# Power_Input.net
KiCad netlist of a schematic drawn in Altium Designer
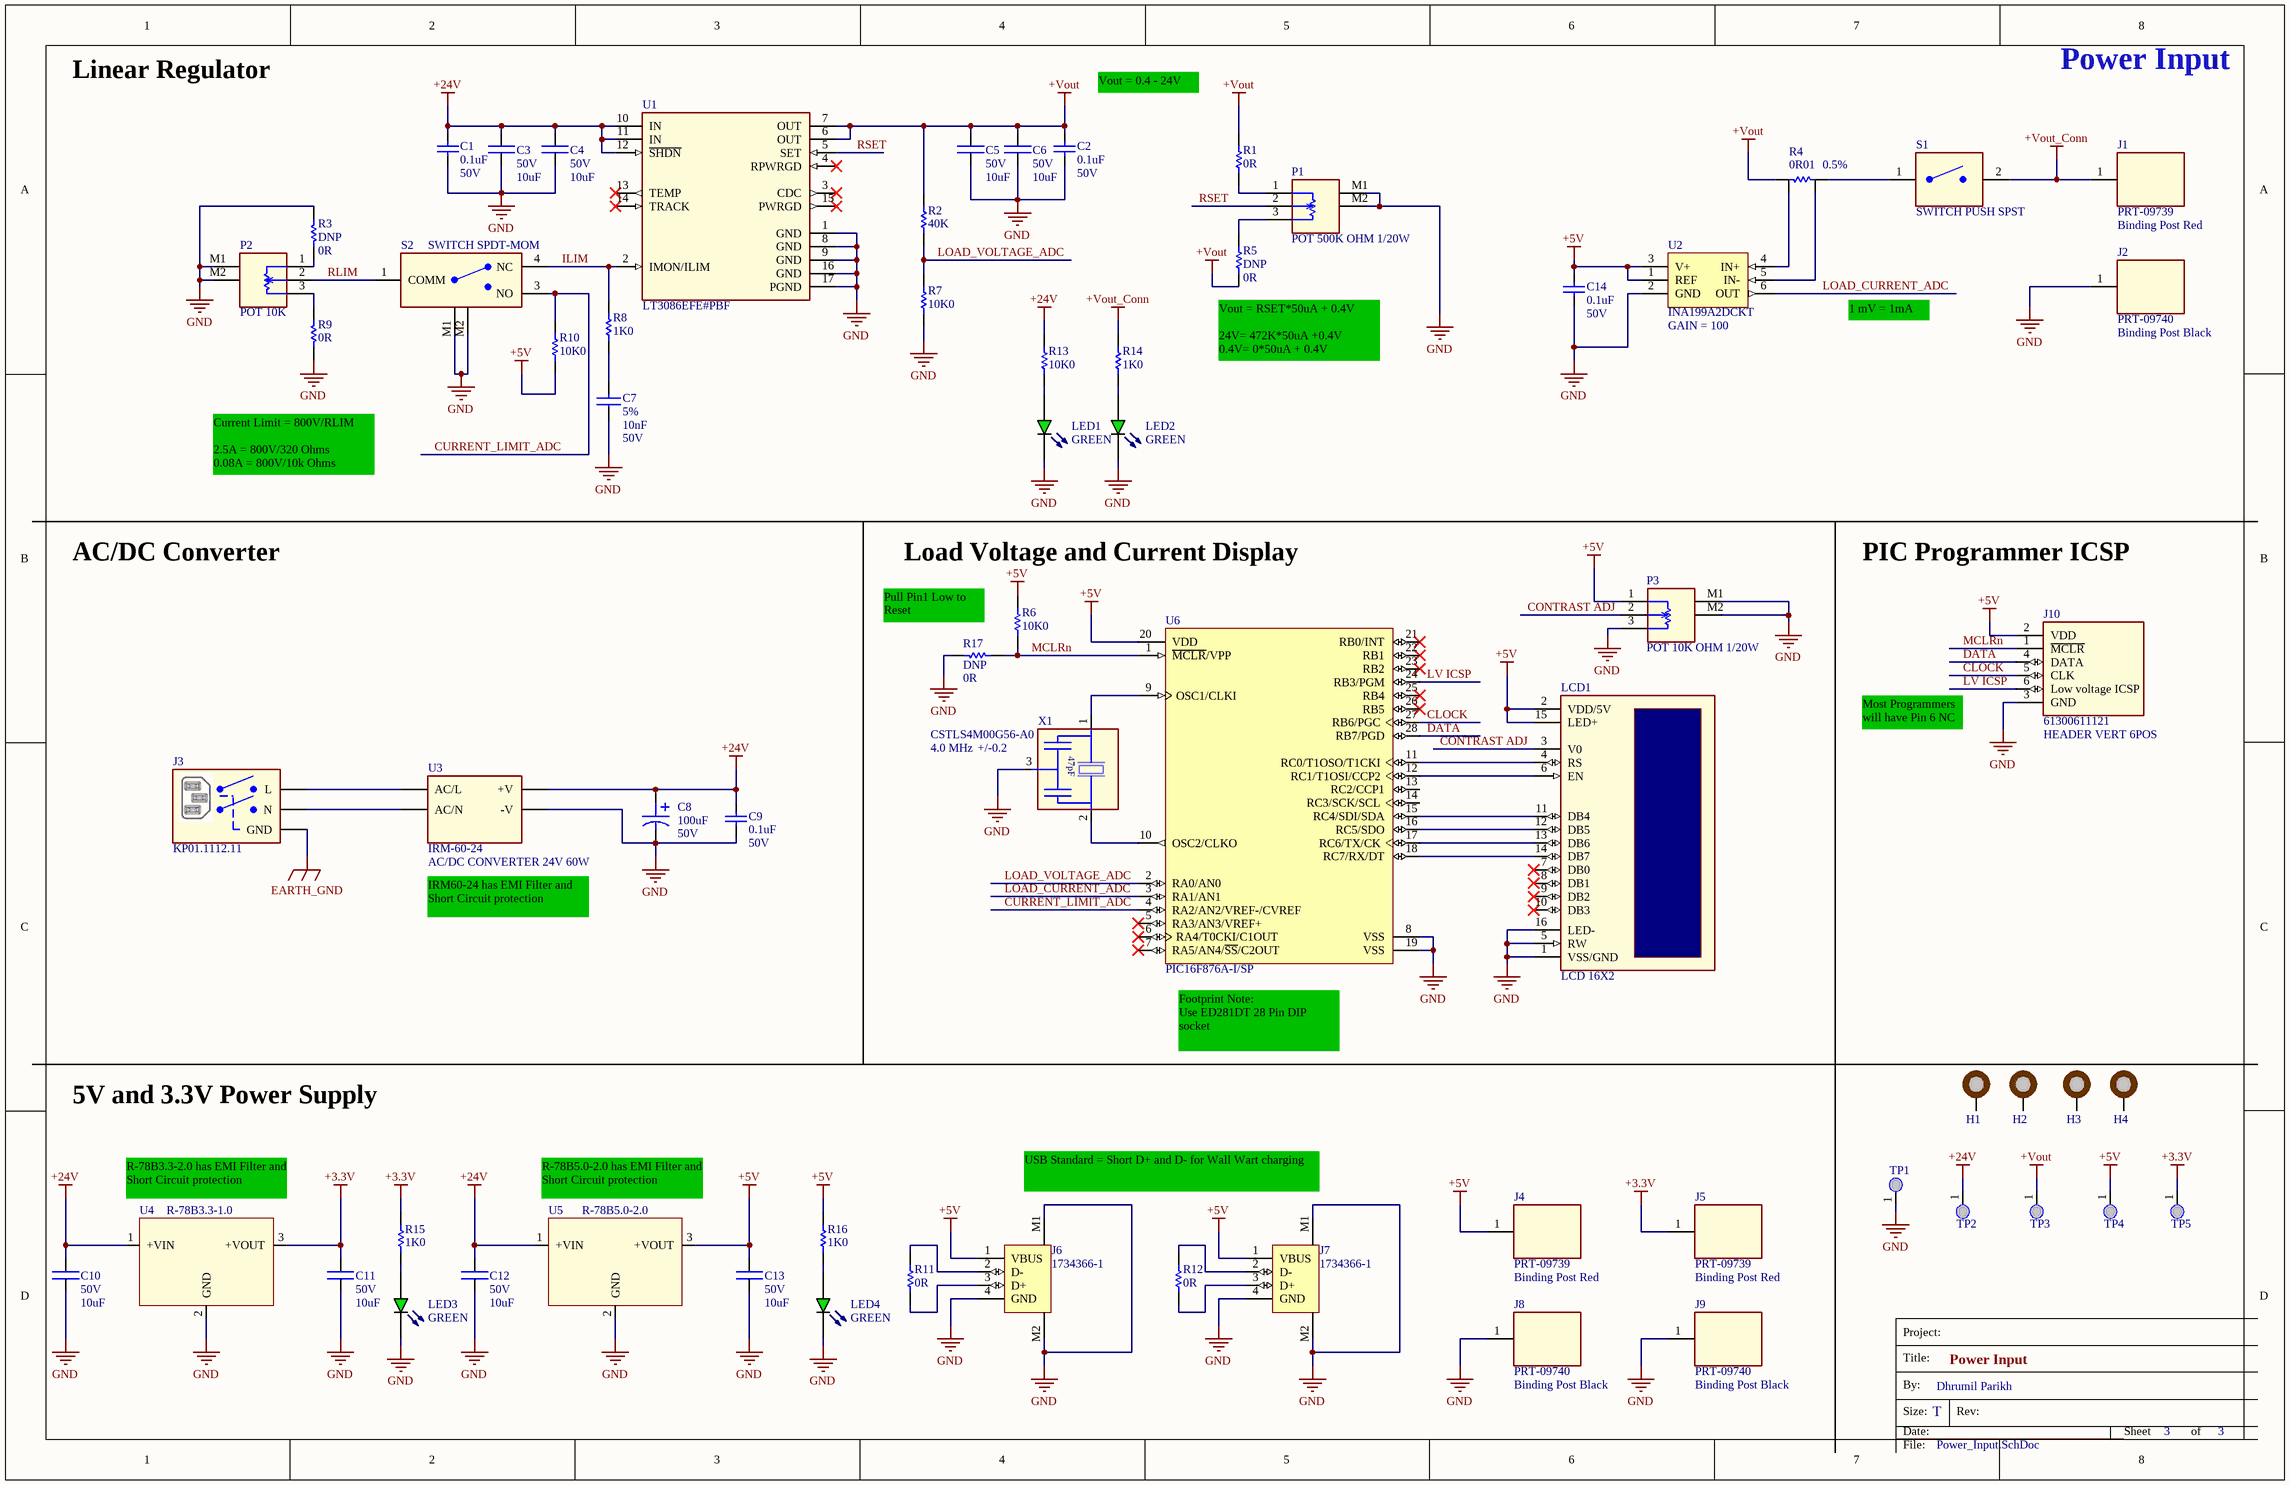
[diagram p0: Power_Input.SchDoc]

(export (version "E")
  (design (tool "Eeschema 10.0.6"))
  (components
    (comp (ref "C1")
      (value "0.1uF")
      (footprint "CAPC1005X06N")
      (description "CAP CER 0.1UF 50V X7R 0402")
      (fields
        (field (name "MFG") "Taiyo Yuden")
        (field (name "MFG_PART_NO") "UMK105B7104KVHF")
        (field (name "VOLTAGE") "50V")
      )
      (libsource (lib "PowerSupply") (part "CAP CER 0.1UF 50V X7R 0402"))
    )
    (comp (ref "C2")
      (value "0.1uF")
      (footprint "CAPC1005X06N")
      (description "CAP CER 0.1UF 50V X7R 0402")
      (fields
        (field (name "MFG") "Taiyo Yuden")
        (field (name "MFG_PART_NO") "UMK105B7104KVHF")
        (field (name "VOLTAGE") "50V")
      )
      (libsource (lib "PowerSupply") (part "CAP CER 0.1UF 50V X7R 0402"))
    )
    (comp (ref "C3")
      (value "10uF")
      (footprint "CAPC3225X28N")
      (description "CAP CER 10UF 50V X7S 1210")
      (fields
        (field (name "MFG") "Taiyo Yuden")
        (field (name "MFG_PART_NO") "UMK325C7106MM-T")
        (field (name "VOLTAGE") "50V")
      )
      (libsource (lib "PowerSupply") (part "CAP CER 10UF 50V X7S 1210"))
    )
    (comp (ref "C4")
      (value "10uF")
      (footprint "CAPC3225X28N")
      (description "CAP CER 10UF 50V X7S 1210")
      (fields
        (field (name "MFG") "Taiyo Yuden")
        (field (name "MFG_PART_NO") "UMK325C7106MM-T")
        (field (name "VOLTAGE") "50V")
      )
      (libsource (lib "PowerSupply") (part "CAP CER 10UF 50V X7S 1210"))
    )
    (comp (ref "C5")
      (value "10uF")
      (footprint "CAPC3225X28N")
      (description "CAP CER 10UF 50V X7S 1210")
      (fields
        (field (name "MFG") "Taiyo Yuden")
        (field (name "MFG_PART_NO") "UMK325C7106MM-T")
        (field (name "VOLTAGE") "50V")
      )
      (libsource (lib "PowerSupply") (part "CAP CER 10UF 50V X7S 1210"))
    )
    (comp (ref "C6")
      (value "10uF")
      (footprint "CAPC3225X28N")
      (description "CAP CER 10UF 50V X7S 1210")
      (fields
        (field (name "MFG") "Taiyo Yuden")
        (field (name "MFG_PART_NO") "UMK325C7106MM-T")
        (field (name "VOLTAGE") "50V")
      )
      (libsource (lib "PowerSupply") (part "CAP CER 10UF 50V X7S 1210"))
    )
    (comp (ref "C7")
      (value "10nF")
      (footprint "CAPC1608X09N")
      (description "CAP CER 10000PF 50V 5% C0G 0603")
      (fields
        (field (name "MFG") "Murata")
        (field (name "MFG_PART_NO") "GRM1885C1H103JA01D")
        (field (name "TOLERANCE") "5%")
        (field (name "VOLTAGE") "50V")
      )
      (libsource (lib "PowerSupply") (part "CAP CER 10000PF 50V 5% C0G 0603"))
    )
    (comp (ref "C8")
      (value "100uF")
      (footprint "EEH-ZA1H101P_CAPAE1030X1050N")
      (description "CAP ALUM POLY HYB 100UF 20% 50V SMD")
      (fields
        (field (name "MFG") "Panasonic Electronic Components")
        (field (name "MFG_PART_NO") "EEH-ZA1H101P")
        (field (name "VOLTAGE") "50V")
      )
      (libsource (lib "PowerSupply") (part "CAP ALUM POLY HYB 100UF 50V SMD"))
    )
    (comp (ref "C9")
      (value "0.1uF")
      (footprint "CAPC1005X06N")
      (description "CAP CER 0.1UF 50V X7R 0402")
      (fields
        (field (name "MFG") "Taiyo Yuden")
        (field (name "MFG_PART_NO") "UMK105B7104KVHF")
        (field (name "VOLTAGE") "50V")
      )
      (libsource (lib "PowerSupply") (part "CAP CER 0.1UF 50V X7R 0402"))
    )
    (comp (ref "C10")
      (value "10uF")
      (footprint "CAPC3225X28N")
      (description "CAP CER 10UF 50V X7S 1210")
      (fields
        (field (name "MFG") "Taiyo Yuden")
        (field (name "MFG_PART_NO") "UMK325C7106MM-T")
        (field (name "VOLTAGE") "50V")
      )
      (libsource (lib "PowerSupply") (part "CAP CER 10UF 50V X7S 1210"))
    )
    (comp (ref "C11")
      (value "10uF")
      (footprint "CAPC3225X28N")
      (description "CAP CER 10UF 50V X7S 1210")
      (fields
        (field (name "MFG") "Taiyo Yuden")
        (field (name "MFG_PART_NO") "UMK325C7106MM-T")
        (field (name "VOLTAGE") "50V")
      )
      (libsource (lib "PowerSupply") (part "CAP CER 10UF 50V X7S 1210"))
    )
    (comp (ref "C12")
      (value "10uF")
      (footprint "CAPC3225X28N")
      (description "CAP CER 10UF 50V X7S 1210")
      (fields
        (field (name "MFG") "Taiyo Yuden")
        (field (name "MFG_PART_NO") "UMK325C7106MM-T")
        (field (name "VOLTAGE") "50V")
      )
      (libsource (lib "PowerSupply") (part "CAP CER 10UF 50V X7S 1210"))
    )
    (comp (ref "C13")
      (value "10uF")
      (footprint "CAPC3225X28N")
      (description "CAP CER 10UF 50V X7S 1210")
      (fields
        (field (name "MFG") "Taiyo Yuden")
        (field (name "MFG_PART_NO") "UMK325C7106MM-T")
        (field (name "VOLTAGE") "50V")
      )
      (libsource (lib "PowerSupply") (part "CAP CER 10UF 50V X7S 1210"))
    )
    (comp (ref "C14")
      (value "0.1uF")
      (footprint "CAPC1005X06N")
      (description "CAP CER 0.1UF 50V X7R 0402")
      (fields
        (field (name "MFG") "Taiyo Yuden")
        (field (name "MFG_PART_NO") "UMK105B7104KVHF")
        (field (name "VOLTAGE") "50V")
      )
      (libsource (lib "PowerSupply") (part "CAP CER 0.1UF 50V X7R 0402"))
    )
    (comp (ref "H1")
      (value "MTG_HOLE PTH, 3.0mm")
      (footprint "MH_PTH_H3.0mmXP6.0mm")
      (description "PTH, 3.0mm")
      (libsource (lib "PowerSupply") (part "MTG_HOLE PTH, 3.0mm"))
    )
    (comp (ref "H2")
      (value "MTG_HOLE PTH, 3.0mm")
      (footprint "MH_PTH_H3.0mmXP6.0mm")
      (description "PTH, 3.0mm")
      (libsource (lib "PowerSupply") (part "MTG_HOLE PTH, 3.0mm"))
    )
    (comp (ref "H3")
      (value "MTG_HOLE PTH, 3.0mm")
      (footprint "MH_PTH_H3.0mmXP6.0mm")
      (description "PTH, 3.0mm")
      (libsource (lib "PowerSupply") (part "MTG_HOLE PTH, 3.0mm"))
    )
    (comp (ref "H4")
      (value "MTG_HOLE PTH, 3.0mm")
      (footprint "MH_PTH_H3.0mmXP6.0mm")
      (description "PTH, 3.0mm")
      (libsource (lib "PowerSupply") (part "MTG_HOLE PTH, 3.0mm"))
    )
    (comp (ref "J1")
      (value "Binding Post Red")
      (description "CONN BIND POST KNURLED RED")
      (fields (field (name "MFG") "SparkFun Electronics") (field (name "MFG_PART_NO") "PRT-09739"))
      (libsource (lib "PowerSupply") (part "CONN BIND POST KNURLED RED"))
    )
    (comp (ref "J2")
      (value "Binding Post Black")
      (description "CONN BIND POST KNURLED BLACK")
      (fields (field (name "MFG") "SparkFun Electronics") (field (name "MFG_PART_NO") "PRT-09740"))
      (libsource (lib "PowerSupply") (part "CONN BIND POST KNURLED BLACK"))
    )
    (comp (ref "J3")
      (value "PWR ENT MOD RCPT IEC320-C14 PNL")
      (fields (field (name "MFG") "Schurter Inc.") (field (name "MFG_PART_NO") "KP01.1112.11"))
      (libsource (lib "PowerSupply") (part "PWR ENT MOD RCPT IEC320-C14 PNL"))
    )
    (comp (ref "J4")
      (value "Binding Post Red")
      (description "CONN BIND POST KNURLED RED")
      (fields (field (name "MFG") "SparkFun Electronics") (field (name "MFG_PART_NO") "PRT-09739"))
      (libsource (lib "PowerSupply") (part "CONN BIND POST KNURLED RED"))
    )
    (comp (ref "J5")
      (value "Binding Post Red")
      (description "CONN BIND POST KNURLED RED")
      (fields (field (name "MFG") "SparkFun Electronics") (field (name "MFG_PART_NO") "PRT-09739"))
      (libsource (lib "PowerSupply") (part "CONN BIND POST KNURLED RED"))
    )
    (comp (ref "J6")
      (value "1734366-1")
      (footprint "CONN_CUI_UJ2-AV-x-SMT")
      (description "CONN RCPT USB2.0 TYPEA 4POS VERT")
      (fields (field (name "MFG") "TE Connectivity AMP Connectors"))
      (libsource (lib "PowerSupply") (part "CONN RCPT USB2.0 TYPEA 4POS VERT"))
    )
    (comp (ref "J7")
      (value "1734366-1")
      (footprint "CONN_CUI_UJ2-AV-x-SMT")
      (description "CONN RCPT USB2.0 TYPEA 4POS VERT")
      (fields (field (name "MFG") "TE Connectivity AMP Connectors"))
      (libsource (lib "PowerSupply") (part "CONN RCPT USB2.0 TYPEA 4POS VERT"))
    )
    (comp (ref "J8")
      (value "Binding Post Black")
      (description "CONN BIND POST KNURLED BLACK")
      (fields (field (name "MFG") "SparkFun Electronics") (field (name "MFG_PART_NO") "PRT-09740"))
      (libsource (lib "PowerSupply") (part "CONN BIND POST KNURLED BLACK"))
    )
    (comp (ref "J9")
      (value "Binding Post Black")
      (description "CONN BIND POST KNURLED BLACK")
      (fields (field (name "MFG") "SparkFun Electronics") (field (name "MFG_PART_NO") "PRT-09740"))
      (libsource (lib "PowerSupply") (part "CONN BIND POST KNURLED BLACK"))
    )
    (comp (ref "J10")
      (value "HEADER VERT 6POS")
      (description "CONN HEADER VERT 6POS 2.54MM")
      (fields (field (name "MFG") "Wurth Electronics Inc.") (field (name "MFG_PART_NO") "61300611121"))
      (libsource (lib "PowerSupply") (part "CONN HEADER VERT 6POS 2.54MM"))
    )
    (comp (ref "LCD1")
      (value "LCD 16X2")
      (description "STANDARD LCD 16X2 + EXTRAS")
      (fields (field (name "MFG") "Adafruit Industries LLC") (field (name "MFG_PART_NO") "181"))
      (libsource (lib "PowerSupply") (part "STANDARD LCD 16X2 + EXTRAS"))
    )
    (comp (ref "LED1")
      (value "GREEN")
      (footprint "LED LTST-C190KGKT")
      (description "LED SUPER GREEN CLEAR 0603 SMD")
      (fields (field (name "MFG") "Lite-On") (field (name "MFG_PART_NO") "LTST-C190KGKT"))
      (libsource (lib "PowerSupply") (part "LED GREEN"))
    )
    (comp (ref "LED2")
      (value "GREEN")
      (footprint "LED LTST-C190KGKT")
      (description "LED SUPER GREEN CLEAR 0603 SMD")
      (fields (field (name "MFG") "Lite-On") (field (name "MFG_PART_NO") "LTST-C190KGKT"))
      (libsource (lib "PowerSupply") (part "LED GREEN"))
    )
    (comp (ref "LED3")
      (value "GREEN")
      (footprint "LED LTST-C190KGKT")
      (description "LED SUPER GREEN CLEAR 0603 SMD")
      (fields (field (name "MFG") "Lite-On") (field (name "MFG_PART_NO") "LTST-C190KGKT"))
      (libsource (lib "PowerSupply") (part "LED GREEN"))
    )
    (comp (ref "LED4")
      (value "GREEN")
      (footprint "LED LTST-C190KGKT")
      (description "LED SUPER GREEN CLEAR 0603 SMD")
      (fields (field (name "MFG") "Lite-On") (field (name "MFG_PART_NO") "LTST-C190KGKT"))
      (libsource (lib "PowerSupply") (part "LED GREEN"))
    )
    (comp (ref "P1")
      (value "POT 500K OHM 1/20W")
      (description "POT 500K OHM 1/20W CARBON LOG")
      (fields (field (name "MFG") "Bourns Inc.") (field (name "MFG_PART_NO") "PTV09A-4020F-A504"))
      (libsource (lib "PowerSupply") (part "POT 500K OHM 1/20W CARBON LOG"))
    )
    (comp (ref "P2")
      (value "POT 10K")
      (description "POT 10K OHM 1/20W CARBON LOG")
      (fields (field (name "MFG") "Bourns Inc.") (field (name "MFG_PART_NO") "PTV09A-4020F-A103"))
      (libsource (lib "") (part "POT 10K OHM 1/20W CARBON LOG_1"))
    )
    (comp (ref "P3")
      (value "POT 10K OHM 1/20W")
      (description "POT 10K OHM 1/20W CARBON LOG")
      (fields (field (name "MFG") "Bourns Inc.") (field (name "MFG_PART_NO") "PTV09A-4020F-A103"))
      (libsource (lib "PowerSupply") (part "POT 10K OHM 1/20W CARBON LOG"))
    )
    (comp (ref "R1")
      (value "0R")
      (footprint "RESC2012X07N")
      (description "RES SMD 0 OHM JUMPER 1/8W 0805")
      (fields (field (name "MFG") "Panasonic") (field (name "MFG_PART_NO") "ERJ-6GEY0R00V"))
      (libsource (lib "PowerSupply") (part "RES SMD 0 OHM JUMPER 1/8W 0805"))
    )
    (comp (ref "R2")
      (value "40K")
      (footprint "RESC1608X06N")
      (description "RES SMD 40K OHM 0.1% 0.15W 0603")
      (fields (field (name "MFG") "Vishay Thin Film") (field (name "MFG_PART_NO") "PAT0603E4002BST1"))
      (libsource (lib "PowerSupply") (part "RES SMD 40K OHM 0.1% 0.15W 0603"))
    )
    (comp (ref "R3")
      (value "0R")
      (footprint "RESC2012X07N")
      (description "RES SMD 0 OHM JUMPER 1/8W 0805")
      (fields
        (field (name "MFG") "Panasonic")
        (field (name "NOSTUFF") "DNP")
        (field (name "MFG_PART_NO") "ERJ-6GEY0R00V")
      )
      (libsource (lib "PowerSupply") (part "RES SMD 0 OHM JUMPER 1/8W 0805"))
    )
    (comp (ref "R4")
      (value "0R01")
      (description "RES 0.01 OHM 0.5% 1/2W 1206 WIDE")
      (fields
        (field (name "MFG") "Ohmite")
        (field (name "MFG_PART_NO") "FC4TR010DER")
        (field (name "TOLERANCE") "0.5%")
      )
      (libsource (lib "PowerSupply") (part "RES 0.01 OHM 0.5% 1/2W 1206 WIDE"))
    )
    (comp (ref "R5")
      (value "0R")
      (footprint "RESC2012X07N")
      (description "RES SMD 0 OHM JUMPER 1/8W 0805")
      (fields
        (field (name "MFG") "Panasonic")
        (field (name "NOSTUFF") "DNP")
        (field (name "MFG_PART_NO") "ERJ-6GEY0R00V")
      )
      (libsource (lib "PowerSupply") (part "RES SMD 0 OHM JUMPER 1/8W 0805"))
    )
    (comp (ref "R6")
      (value "10K0")
      (footprint "RESC1608X06N")
      (description "RES SMD 10K OHM 1% 1/4W 0603")
      (fields (field (name "MFG") "Rohm") (field (name "MFG_PART_NO") "ESR03EZPF1002"))
      (libsource (lib "PowerSupply") (part "RES SMD 10K OHM 1% 1/4W 0603"))
    )
    (comp (ref "R7")
      (value "10K0")
      (footprint "RESC1608X06N")
      (description "RES SMD 10K OHM 1% 1/4W 0603")
      (fields (field (name "MFG") "Rohm") (field (name "MFG_PART_NO") "ESR03EZPF1002"))
      (libsource (lib "PowerSupply") (part "RES SMD 10K OHM 1% 1/4W 0603"))
    )
    (comp (ref "R8")
      (value "1K0")
      (footprint "RESC1608X06N")
      (description "RES SMD 1K OHM 1% 1/10W 0603")
      (fields (field (name "MFG") "Stackpole") (field (name "MFG_PART_NO") "RMCF0603FT1K00"))
      (libsource (lib "PowerSupply") (part "RES SMD 1K OHM 1% 1/10W 0603"))
    )
    (comp (ref "R9")
      (value "0R")
      (footprint "RESC2012X07N")
      (description "RES SMD 0 OHM JUMPER 1/8W 0805")
      (fields (field (name "MFG") "Panasonic") (field (name "MFG_PART_NO") "ERJ-6GEY0R00V"))
      (libsource (lib "PowerSupply") (part "RES SMD 0 OHM JUMPER 1/8W 0805"))
    )
    (comp (ref "R10")
      (value "10K0")
      (footprint "RESC1608X06N")
      (description "RES SMD 10K OHM 1% 1/4W 0603")
      (fields (field (name "MFG") "Rohm") (field (name "MFG_PART_NO") "ESR03EZPF1002"))
      (libsource (lib "PowerSupply") (part "RES SMD 10K OHM 1% 1/4W 0603"))
    )
    (comp (ref "R11")
      (value "0R")
      (footprint "RESC2012X07N")
      (description "RES SMD 0 OHM JUMPER 1/8W 0805")
      (fields (field (name "MFG") "Panasonic") (field (name "MFG_PART_NO") "ERJ-6GEY0R00V"))
      (libsource (lib "PowerSupply") (part "RES SMD 0 OHM JUMPER 1/8W 0805"))
    )
    (comp (ref "R12")
      (value "0R")
      (footprint "RESC2012X07N")
      (description "RES SMD 0 OHM JUMPER 1/8W 0805")
      (fields (field (name "MFG") "Panasonic") (field (name "MFG_PART_NO") "ERJ-6GEY0R00V"))
      (libsource (lib "PowerSupply") (part "RES SMD 0 OHM JUMPER 1/8W 0805"))
    )
    (comp (ref "R13")
      (value "10K0")
      (footprint "RESC1608X06N")
      (description "RES SMD 10K OHM 1% 1/4W 0603")
      (fields (field (name "MFG") "Rohm") (field (name "MFG_PART_NO") "ESR03EZPF1002"))
      (libsource (lib "PowerSupply") (part "RES SMD 10K OHM 1% 1/4W 0603"))
    )
    (comp (ref "R14")
      (value "1K0")
      (footprint "RESC1608X06N")
      (description "RES SMD 1K OHM 1% 1/10W 0603")
      (fields (field (name "MFG") "Stackpole") (field (name "MFG_PART_NO") "RMCF0603FT1K00"))
      (libsource (lib "PowerSupply") (part "RES SMD 1K OHM 1% 1/10W 0603"))
    )
    (comp (ref "R15")
      (value "1K0")
      (footprint "RESC1608X06N")
      (description "RES SMD 1K OHM 1% 1/10W 0603")
      (fields (field (name "MFG") "Stackpole") (field (name "MFG_PART_NO") "RMCF0603FT1K00"))
      (libsource (lib "PowerSupply") (part "RES SMD 1K OHM 1% 1/10W 0603"))
    )
    (comp (ref "R16")
      (value "1K0")
      (footprint "RESC1608X06N")
      (description "RES SMD 1K OHM 1% 1/10W 0603")
      (fields (field (name "MFG") "Stackpole") (field (name "MFG_PART_NO") "RMCF0603FT1K00"))
      (libsource (lib "PowerSupply") (part "RES SMD 1K OHM 1% 1/10W 0603"))
    )
    (comp (ref "R17")
      (value "0R")
      (footprint "RESC2012X07N")
      (description "RES SMD 0 OHM JUMPER 1/8W 0805")
      (fields
        (field (name "MFG") "Panasonic")
        (field (name "NOSTUFF") "DNP")
        (field (name "MFG_PART_NO") "ERJ-6GEY0R00V")
      )
      (libsource (lib "PowerSupply") (part "RES SMD 0 OHM JUMPER 1/8W 0805"))
    )
    (comp (ref "S1")
      (value "SWITCH PUSH SPST")
      (description "SWITCH PUSH SPST 15A 250V")
      (fields (field (name "MFG") "E-Switch") (field (name "MFG_PART_NO") "PB1973ABLKBLKEF0"))
      (libsource (lib "PowerSupply") (part "SWITCH PUSH SPST 15A 250V"))
    )
    (comp (ref "S2")
      (value "SWITCH SPDT-MOM")
      (description "SWITCH PUSH SPDT 0.025A 50V")
      (fields (field (name "MFG") "C&K") (field (name "MFG_PART_NO") "KS12R22CQD"))
      (libsource (lib "PowerSupply") (part "SWITCH PUSH SPDT 0.025A 50V"))
    )
    (comp (ref "TP1")
      (value "Testpoint Harwin S2751-46R")
      (footprint "TP_HARWIN_2751-46R")
      (description "PC TEST POINT TIN SMD")
      (fields (field (name "MFG") "Harwin Inc.") (field (name "MFG_PART_NO") "S2751-46R"))
      (libsource (lib "PowerSupply") (part "Testpoint Harwin S2751-46R"))
    )
    (comp (ref "TP2")
      (value "Testpoint Harwin S2751-46R")
      (footprint "TP_HARWIN_2751-46R")
      (description "PC TEST POINT TIN SMD")
      (fields (field (name "MFG") "Harwin Inc.") (field (name "MFG_PART_NO") "S2751-46R"))
      (libsource (lib "PowerSupply") (part "Testpoint Harwin S2751-46R"))
    )
    (comp (ref "TP3")
      (value "Testpoint Harwin S2751-46R")
      (footprint "TP_HARWIN_2751-46R")
      (description "PC TEST POINT TIN SMD")
      (fields (field (name "MFG") "Harwin Inc.") (field (name "MFG_PART_NO") "S2751-46R"))
      (libsource (lib "PowerSupply") (part "Testpoint Harwin S2751-46R"))
    )
    (comp (ref "TP4")
      (value "Testpoint Harwin S2751-46R")
      (footprint "TP_HARWIN_2751-46R")
      (description "PC TEST POINT TIN SMD")
      (fields (field (name "MFG") "Harwin Inc.") (field (name "MFG_PART_NO") "S2751-46R"))
      (libsource (lib "PowerSupply") (part "Testpoint Harwin S2751-46R"))
    )
    (comp (ref "TP5")
      (value "Testpoint Harwin S2751-46R")
      (footprint "TP_HARWIN_2751-46R")
      (description "PC TEST POINT TIN SMD")
      (fields (field (name "MFG") "Harwin Inc.") (field (name "MFG_PART_NO") "S2751-46R"))
      (libsource (lib "PowerSupply") (part "Testpoint Harwin S2751-46R"))
    )
    (comp (ref "U1")
      (value "LT3086EFE#PBF")
      (description "IC REG LIN POS ADJ 2.1A 16TSSOP")
      (fields (field (name "MFG") "Linear Technology/Analog Devices"))
      (libsource (lib "PowerSupply") (part "IC REG LIN POS ADJ 2.1A 16TSSOP"))
    )
    (comp (ref "U2")
      (value "INA199A2DCKT")
      (description "IC OPAMP CURR SENSE 14KHZ SC70-6")
      (fields (field (name "MFG") "TE Connectivity AMP Connectors") (field (name "GAIN") "GAIN = 100"))
      (libsource (lib "PowerSupply") (part "IC OPAMP CURR SENSE 14KHZ SC70-6"))
    )
    (comp (ref "U3")
      (value "AC/DC CONVERTER 24V 60W")
      (fields (field (name "MFG") "MEAN WELL USA Inc.") (field (name "MFG_PART_NO") "IRM-60-24"))
      (libsource (lib "PowerSupply") (part "AC/DC CONVERTER 24V 60W"))
    )
    (comp (ref "U4")
      (value "DC DC CONVERTER 3.3V 3W")
      (footprint "Miroculus:DC_Module_TH_R-78Bxx-1.0")
      (fields (field (name "MFG") "Recom Power") (field (name "MFG_PART_NO") "R-78B3.3-1.0"))
      (libsource (lib "PowerSupply") (part "DC DC CONVERTER 3.3V 3W"))
    )
    (comp (ref "U5")
      (value "DC DC CONVERTER 5V 10W")
      (footprint "Miroculus:DC_Module_TH_R-78Bxx-1.0")
      (fields (field (name "MFG") "Recom Power") (field (name "MFG_PART_NO") "R-78B5.0-2.0"))
      (libsource (lib "PowerSupply") (part "DC DC CONVERTER 5V 10W"))
    )
    (comp (ref "U6")
      (value "PIC16F876A-I/SP")
      (footprint "SPDIP300-SP28")
      (fields (field (name "MFG") "Microchip Technology"))
      (libsource (lib "PowerSupply") (part "PIC16F876A-I/SP"))
    )
    (comp (ref "X1")
      (value "4.0 MHz")
      (description "CER RESONATOR")
      (fields
        (field (name "TOLERANCE") "+/-0.5")
        (field (name "MFG_PART_NO") "CSTLS4M00G56-A0")
        (field (name "STABILITY") "+/-0.2")
      )
      (libsource (lib "PowerSupply") (part "CER RESONATOR"))
    )
  )
  (nets
    (net (code "1") (name "+3.3V") (class "Default")
      (node (ref "C11") (pin "1") (pinfunction "1_1") (pintype "passive"))
      (node (ref "J5") (pin "1") (pintype "power_in"))
      (node (ref "R15") (pin "2") (pinfunction "2_2") (pintype "passive"))
      (node (ref "TP5") (pin "1") (pinfunction "1_1") (pintype "passive"))
      (node (ref "U4") (pin "3") (pinfunction "+VOUT_3") (pintype "power_in"))
    )
    (net (code "2") (name "+5V") (class "Default")
      (node (ref "C13") (pin "1") (pinfunction "1_1") (pintype "passive"))
      (node (ref "C14") (pin "1") (pinfunction "1_1") (pintype "passive"))
      (node (ref "J10") (pin "2") (pinfunction "VDD_2") (pintype "power_in"))
      (node (ref "J4") (pin "1") (pintype "power_in"))
      (node (ref "J6") (pin "1") (pinfunction "VBUS_1") (pintype "power_in"))
      (node (ref "J7") (pin "1") (pinfunction "VBUS_1") (pintype "power_in"))
      (node (ref "LCD1") (pin "15") (pinfunction "LED+_15") (pintype "power_in"))
      (node (ref "LCD1") (pin "2") (pinfunction "VDD/5V_2") (pintype "power_in"))
      (node (ref "P3") (pin "1") (pintype "power_in"))
      (node (ref "R10") (pin "1") (pinfunction "1_1") (pintype "passive"))
      (node (ref "R16") (pin "2") (pinfunction "2_2") (pintype "passive"))
      (node (ref "R6") (pin "2") (pinfunction "2_2") (pintype "passive"))
      (node (ref "TP4") (pin "1") (pinfunction "1_1") (pintype "passive"))
      (node (ref "U2") (pin "1") (pinfunction "REF_1") (pintype "power_in"))
      (node (ref "U2") (pin "3") (pinfunction "V+_3") (pintype "power_in"))
      (node (ref "U5") (pin "3") (pinfunction "+VOUT_3") (pintype "power_in"))
      (node (ref "U6") (pin "20") (pinfunction "VDD_20") (pintype "power_in"))
    )
    (net (code "3") (name "+24V") (class "Default")
      (node (ref "C1") (pin "1") (pinfunction "1_1") (pintype "passive"))
      (node (ref "C10") (pin "1") (pinfunction "1_1") (pintype "passive"))
      (node (ref "C12") (pin "1") (pinfunction "1_1") (pintype "passive"))
      (node (ref "C3") (pin "1") (pinfunction "1_1") (pintype "passive"))
      (node (ref "C4") (pin "1") (pinfunction "1_1") (pintype "passive"))
      (node (ref "C8") (pin "1") (pinfunction "1_1") (pintype "passive"))
      (node (ref "C9") (pin "1") (pinfunction "1_1") (pintype "passive"))
      (node (ref "R13") (pin "2") (pinfunction "2_2") (pintype "passive"))
      (node (ref "TP2") (pin "1") (pinfunction "1_1") (pintype "passive"))
      (node (ref "U1") (pin "10") (pinfunction "IN_10") (pintype "power_in"))
      (node (ref "U1") (pin "11") (pinfunction "IN_11") (pintype "power_in"))
      (node (ref "U1") (pin "12") (pinfunction "~{SHDN}_12") (pintype "input"))
      (node (ref "U3") (pin "+V") (pinfunction "+V_+V") (pintype "power_in"))
      (node (ref "U4") (pin "1") (pinfunction "+VIN_1") (pintype "power_in"))
      (node (ref "U5") (pin "1") (pinfunction "+VIN_1") (pintype "power_in"))
    )
    (net (code "4") (name "+Vout") (class "Default")
      (node (ref "C2") (pin "1") (pinfunction "1_1") (pintype "passive"))
      (node (ref "C5") (pin "1") (pinfunction "1_1") (pintype "passive"))
      (node (ref "C6") (pin "1") (pinfunction "1_1") (pintype "passive"))
      (node (ref "R1") (pin "2") (pinfunction "2_2") (pintype "passive"))
      (node (ref "R2") (pin "2") (pinfunction "2_2") (pintype "passive"))
      (node (ref "R4") (pin "1") (pinfunction "1_1") (pintype "passive"))
      (node (ref "R5") (pin "1") (pinfunction "1_1") (pintype "passive"))
      (node (ref "TP3") (pin "1") (pinfunction "1_1") (pintype "passive"))
      (node (ref "U1") (pin "6") (pinfunction "OUT_6") (pintype "power_in"))
      (node (ref "U1") (pin "7") (pinfunction "OUT_7") (pintype "power_in"))
    )
    (net (code "5") (name "+Vout_Conn") (class "Default")
      (node (ref "J1") (pin "1") (pintype "power_in"))
      (node (ref "R14") (pin "2") (pinfunction "2_2") (pintype "passive"))
      (node (ref "S1") (pin "2") (pintype "power_in"))
    )
    (net (code "6") (name "/CLOCK") (class "Default")
      (node (ref "J10") (pin "5") (pinfunction "CLK_5") (pintype "bidirectional"))
      (node (ref "U6") (pin "27") (pinfunction "RB6/PGC_27") (pintype "bidirectional"))
    )
    (net (code "7") (name "/CONTRAST ADJ") (class "Default")
      (node (ref "LCD1") (pin "3") (pinfunction "V0_3") (pintype "power_in"))
      (node (ref "P3") (pin "2") (pintype "power_in"))
    )
    (net (code "8") (name "/CURRENT_LIMIT_ADC") (class "Default")
      (node (ref "R10") (pin "2") (pinfunction "2_2") (pintype "passive"))
      (node (ref "S2") (pin "3") (pinfunction "NO_3") (pintype "power_in"))
      (node (ref "U6") (pin "4") (pinfunction "RA2/AN2/VREF-/CVREF_4") (pintype "bidirectional"))
    )
    (net (code "9") (name "/DATA") (class "Default")
      (node (ref "J10") (pin "4") (pinfunction "DATA_4") (pintype "bidirectional"))
      (node (ref "U6") (pin "28") (pinfunction "RB7/PGD_28") (pintype "bidirectional"))
    )
    (net (code "10") (name "/ILIM") (class "Default")
      (node (ref "R8") (pin "2") (pinfunction "2_2") (pintype "passive"))
      (node (ref "S2") (pin "4") (pinfunction "NC_4") (pintype "power_in"))
      (node (ref "U1") (pin "2") (pinfunction "IMON/ILIM_2") (pintype "input"))
    )
    (net (code "11") (name "/LOAD_CURRENT_ADC") (class "Default")
      (node (ref "U2") (pin "6") (pinfunction "OUT_6") (pintype "output"))
      (node (ref "U6") (pin "3") (pinfunction "RA1/AN1_3") (pintype "bidirectional"))
    )
    (net (code "12") (name "/LOAD_VOLTAGE_ADC") (class "Default")
      (node (ref "R2") (pin "1") (pinfunction "1_1") (pintype "passive"))
      (node (ref "R7") (pin "2") (pinfunction "2_2") (pintype "passive"))
      (node (ref "U6") (pin "2") (pinfunction "RA0/AN0_2") (pintype "bidirectional"))
    )
    (net (code "13") (name "/LV ICSP") (class "Default")
      (node (ref "J10") (pin "6") (pinfunction "Low_voltage_ICSP_6") (pintype "bidirectional"))
      (node (ref "U6") (pin "24") (pinfunction "RB3/PGM_24") (pintype "bidirectional"))
    )
    (net (code "14") (name "/MCLRn") (class "Default")
      (node (ref "J10") (pin "1") (pinfunction "~{MCLR}_1") (pintype "power_in"))
      (node (ref "R17") (pin "1") (pinfunction "1_1") (pintype "passive"))
      (node (ref "R6") (pin "1") (pinfunction "1_1") (pintype "passive"))
      (node (ref "U6") (pin "1") (pinfunction "~{MCLR}/VPP_1") (pintype "input"))
    )
    (net (code "15") (name "/RLIM") (class "Default")
      (node (ref "P2") (pin "2") (pintype "power_in"))
      (node (ref "S2") (pin "1") (pinfunction "COMM_1") (pintype "power_in"))
    )
    (net (code "16") (name "/RSET") (class "Default")
      (node (ref "P1") (pin "2") (pintype "power_in"))
      (node (ref "U1") (pin "5") (pinfunction "SET_5") (pintype "input"))
    )
    (net (code "17") (name "EARTH_GND") (class "Default")
      (node (ref "J3") (pin "GND") (pinfunction "GND_GND") (pintype "power_in"))
    )
    (net (code "18") (name "GND") (class "Default")
      (node (ref "C1") (pin "2") (pinfunction "2_2") (pintype "passive"))
      (node (ref "C10") (pin "2") (pinfunction "2_2") (pintype "passive"))
      (node (ref "C11") (pin "2") (pinfunction "2_2") (pintype "passive"))
      (node (ref "C12") (pin "2") (pinfunction "2_2") (pintype "passive"))
      (node (ref "C13") (pin "2") (pinfunction "2_2") (pintype "passive"))
      (node (ref "C14") (pin "2") (pinfunction "2_2") (pintype "passive"))
      (node (ref "C2") (pin "2") (pinfunction "2_2") (pintype "passive"))
      (node (ref "C3") (pin "2") (pinfunction "2_2") (pintype "passive"))
      (node (ref "C4") (pin "2") (pinfunction "2_2") (pintype "passive"))
      (node (ref "C5") (pin "2") (pinfunction "2_2") (pintype "passive"))
      (node (ref "C6") (pin "2") (pinfunction "2_2") (pintype "passive"))
      (node (ref "C7") (pin "1") (pinfunction "1_1") (pintype "passive"))
      (node (ref "C8") (pin "2") (pinfunction "2_2") (pintype "passive"))
      (node (ref "C9") (pin "2") (pinfunction "2_2") (pintype "passive"))
      (node (ref "J10") (pin "3") (pinfunction "GND_3") (pintype "power_in"))
      (node (ref "J2") (pin "1") (pintype "power_in"))
      (node (ref "J6") (pin "4") (pinfunction "GND_4") (pintype "power_in"))
      (node (ref "J6") (pin "M1") (pinfunction "M1_M1") (pintype "passive"))
      (node (ref "J6") (pin "M2") (pinfunction "M2_M2") (pintype "passive"))
      (node (ref "J7") (pin "4") (pinfunction "GND_4") (pintype "power_in"))
      (node (ref "J7") (pin "M1") (pinfunction "M1_M1") (pintype "passive"))
      (node (ref "J7") (pin "M2") (pinfunction "M2_M2") (pintype "passive"))
      (node (ref "J8") (pin "1") (pintype "power_in"))
      (node (ref "J9") (pin "1") (pintype "power_in"))
      (node (ref "LCD1") (pin "1") (pinfunction "VSS/GND_1") (pintype "power_in"))
      (node (ref "LCD1") (pin "16") (pinfunction "LED-_16") (pintype "power_in"))
      (node (ref "LCD1") (pin "5") (pinfunction "RW_5") (pintype "input"))
      (node (ref "LED1") (pin "K") (pinfunction "K_K") (pintype "passive"))
      (node (ref "LED2") (pin "K") (pinfunction "K_K") (pintype "passive"))
      (node (ref "LED3") (pin "K") (pinfunction "K_K") (pintype "passive"))
      (node (ref "LED4") (pin "K") (pinfunction "K_K") (pintype "passive"))
      (node (ref "P1") (pin "M1") (pintype "power_in"))
      (node (ref "P1") (pin "M2") (pintype "power_in"))
      (node (ref "P2") (pin "M1") (pintype "power_in"))
      (node (ref "P2") (pin "M2") (pintype "power_in"))
      (node (ref "P3") (pin "3") (pintype "power_in"))
      (node (ref "P3") (pin "M1") (pintype "power_in"))
      (node (ref "P3") (pin "M2") (pintype "power_in"))
      (node (ref "R17") (pin "2") (pinfunction "2_2") (pintype "passive"))
      (node (ref "R3") (pin "2") (pinfunction "2_2") (pintype "passive"))
      (node (ref "R7") (pin "1") (pinfunction "1_1") (pintype "passive"))
      (node (ref "R9") (pin "1") (pinfunction "1_1") (pintype "passive"))
      (node (ref "S2") (pin "M1") (pintype "power_in"))
      (node (ref "S2") (pin "M2") (pintype "power_in"))
      (node (ref "TP1") (pin "1") (pinfunction "1_1") (pintype "passive"))
      (node (ref "U1") (pin "1") (pinfunction "GND_1") (pintype "power_in"))
      (node (ref "U1") (pin "16") (pinfunction "GND_16") (pintype "power_in"))
      (node (ref "U1") (pin "17") (pinfunction "PGND_17") (pintype "power_in"))
      (node (ref "U1") (pin "8") (pinfunction "GND_8") (pintype "power_in"))
      (node (ref "U1") (pin "9") (pinfunction "GND_9") (pintype "power_in"))
      (node (ref "U2") (pin "2") (pinfunction "GND_2") (pintype "power_in"))
      (node (ref "U3") (pin "-V") (pinfunction "-V_-V") (pintype "power_in"))
      (node (ref "U4") (pin "2") (pinfunction "GND_2") (pintype "power_in"))
      (node (ref "U5") (pin "2") (pinfunction "GND_2") (pintype "power_in"))
      (node (ref "U6") (pin "19") (pinfunction "VSS_19") (pintype "power_in"))
      (node (ref "U6") (pin "8") (pinfunction "VSS_8") (pintype "power_in"))
      (node (ref "X1") (pin "3") (pintype "passive"))
    )
    (net (code "19") (name "Net-(C7-Pad2)") (class "Default")
      (node (ref "C7") (pin "2") (pinfunction "2_2") (pintype "passive"))
      (node (ref "R8") (pin "1") (pinfunction "1_1") (pintype "passive"))
    )
    (net (code "20") (name "Net-(J3-PadL)") (class "Default")
      (node (ref "J3") (pin "L") (pinfunction "L_L") (pintype "power_in"))
      (node (ref "U3") (pin "AC/L") (pinfunction "AC/L_AC/L") (pintype "power_in"))
    )
    (net (code "21") (name "Net-(J3-PadN)") (class "Default")
      (node (ref "J3") (pin "N") (pinfunction "N_N") (pintype "power_in"))
      (node (ref "U3") (pin "AC/N") (pinfunction "AC/N_AC/N") (pintype "power_in"))
    )
    (net (code "22") (name "Net-(J6-D+)") (class "Default")
      (node (ref "J6") (pin "3") (pinfunction "D+_3") (pintype "bidirectional"))
      (node (ref "R11") (pin "1") (pinfunction "1_1") (pintype "passive"))
    )
    (net (code "23") (name "Net-(J6-D-)") (class "Default")
      (node (ref "J6") (pin "2") (pinfunction "D-_2") (pintype "bidirectional"))
      (node (ref "R11") (pin "2") (pinfunction "2_2") (pintype "passive"))
    )
    (net (code "24") (name "Net-(J7-D+)") (class "Default")
      (node (ref "J7") (pin "3") (pinfunction "D+_3") (pintype "bidirectional"))
      (node (ref "R12") (pin "1") (pinfunction "1_1") (pintype "passive"))
    )
    (net (code "25") (name "Net-(J7-D-)") (class "Default")
      (node (ref "J7") (pin "2") (pinfunction "D-_2") (pintype "bidirectional"))
      (node (ref "R12") (pin "2") (pinfunction "2_2") (pintype "passive"))
    )
    (net (code "26") (name "Net-(LCD1-DB4)") (class "Default")
      (node (ref "LCD1") (pin "11") (pinfunction "DB4_11") (pintype "bidirectional"))
      (node (ref "U6") (pin "15") (pinfunction "RC4/SDI/SDA_15") (pintype "bidirectional"))
    )
    (net (code "27") (name "Net-(LCD1-DB5)") (class "Default")
      (node (ref "LCD1") (pin "12") (pinfunction "DB5_12") (pintype "bidirectional"))
      (node (ref "U6") (pin "16") (pinfunction "RC5/SDO_16") (pintype "bidirectional"))
    )
    (net (code "28") (name "Net-(LCD1-DB6)") (class "Default")
      (node (ref "LCD1") (pin "13") (pinfunction "DB6_13") (pintype "bidirectional"))
      (node (ref "U6") (pin "17") (pinfunction "RC6/TX/CK_17") (pintype "bidirectional"))
    )
    (net (code "29") (name "Net-(LCD1-DB7)") (class "Default")
      (node (ref "LCD1") (pin "14") (pinfunction "DB7_14") (pintype "bidirectional"))
      (node (ref "U6") (pin "18") (pinfunction "RC7/RX/DT_18") (pintype "bidirectional"))
    )
    (net (code "30") (name "Net-(LCD1-EN)") (class "Default")
      (node (ref "LCD1") (pin "6") (pinfunction "EN_6") (pintype "input"))
      (node (ref "U6") (pin "12") (pinfunction "RC1/T1OSI/CCP2_12") (pintype "bidirectional"))
    )
    (net (code "31") (name "Net-(LCD1-RS)") (class "Default")
      (node (ref "LCD1") (pin "4") (pinfunction "RS_4") (pintype "bidirectional"))
      (node (ref "U6") (pin "11") (pinfunction "RC0/T1OSO/T1CKI_11") (pintype "bidirectional"))
    )
    (net (code "32") (name "Net-(LED1-PadA)") (class "Default")
      (node (ref "LED1") (pin "A") (pinfunction "A_A") (pintype "passive"))
      (node (ref "R13") (pin "1") (pinfunction "1_1") (pintype "passive"))
    )
    (net (code "33") (name "Net-(LED2-PadA)") (class "Default")
      (node (ref "LED2") (pin "A") (pinfunction "A_A") (pintype "passive"))
      (node (ref "R14") (pin "1") (pinfunction "1_1") (pintype "passive"))
    )
    (net (code "34") (name "Net-(LED3-PadA)") (class "Default")
      (node (ref "LED3") (pin "A") (pinfunction "A_A") (pintype "passive"))
      (node (ref "R15") (pin "1") (pinfunction "1_1") (pintype "passive"))
    )
    (net (code "35") (name "Net-(LED4-PadA)") (class "Default")
      (node (ref "LED4") (pin "A") (pinfunction "A_A") (pintype "passive"))
      (node (ref "R16") (pin "1") (pinfunction "1_1") (pintype "passive"))
    )
    (net (code "36") (name "Net-(P1-Pad1)") (class "Default")
      (node (ref "P1") (pin "1") (pintype "power_in"))
      (node (ref "R1") (pin "1") (pinfunction "1_1") (pintype "passive"))
    )
    (net (code "37") (name "Net-(P1-Pad3)") (class "Default")
      (node (ref "P1") (pin "3") (pintype "power_in"))
      (node (ref "R5") (pin "2") (pinfunction "2_2") (pintype "passive"))
    )
    (net (code "38") (name "Net-(P2-Pad1)") (class "Default")
      (node (ref "P2") (pin "1") (pintype "power_in"))
      (node (ref "R3") (pin "1") (pinfunction "1_1") (pintype "passive"))
    )
    (net (code "39") (name "Net-(P2-Pad3)") (class "Default")
      (node (ref "P2") (pin "3") (pintype "power_in"))
      (node (ref "R9") (pin "2") (pinfunction "2_2") (pintype "passive"))
    )
    (net (code "40") (name "Net-(R4-Pad2)") (class "Default")
      (node (ref "R4") (pin "2") (pinfunction "2_2") (pintype "passive"))
      (node (ref "S1") (pin "1") (pintype "power_in"))
    )
    (net (code "41") (name "Net-(U2-IN+)") (class "Default")
      (node (ref "R4") (pin "3") (pinfunction "3_3") (pintype "passive"))
      (node (ref "U2") (pin "4") (pinfunction "IN+_4") (pintype "input"))
    )
    (net (code "42") (name "Net-(U2-IN-)") (class "Default")
      (node (ref "R4") (pin "4") (pinfunction "4_4") (pintype "passive"))
      (node (ref "U2") (pin "5") (pinfunction "IN-_5") (pintype "input"))
    )
    (net (code "43") (name "Net-(U6-OSC1{slash}CLKI)") (class "Default")
      (node (ref "U6") (pin "9") (pinfunction "OSC1/CLKI_9") (pintype "input"))
      (node (ref "X1") (pin "1") (pintype "passive"))
    )
    (net (code "44") (name "Net-(U6-OSC2{slash}CLKO)") (class "Default")
      (node (ref "U6") (pin "10") (pinfunction "OSC2/CLKO_10") (pintype "output"))
      (node (ref "X1") (pin "2") (pintype "passive"))
    )
    (net (code "45") (name "unconnected-(H1-Pad1)") (class "Default")
      (node (ref "H1") (pin "1") (pinfunction "1_1") (pintype "passive"))
    )
    (net (code "46") (name "unconnected-(H2-Pad1)") (class "Default")
      (node (ref "H2") (pin "1") (pinfunction "1_1") (pintype "passive"))
    )
    (net (code "47") (name "unconnected-(H3-Pad1)") (class "Default")
      (node (ref "H3") (pin "1") (pinfunction "1_1") (pintype "passive"))
    )
    (net (code "48") (name "unconnected-(H4-Pad1)") (class "Default")
      (node (ref "H4") (pin "1") (pinfunction "1_1") (pintype "passive"))
    )
    (net (code "49") (name "unconnected-(LCD1-DB0-Pad7)") (class "Default")
      (node (ref "LCD1") (pin "7") (pinfunction "DB0_7") (pintype "bidirectional+no_connect"))
    )
    (net (code "50") (name "unconnected-(LCD1-DB1-Pad8)") (class "Default")
      (node (ref "LCD1") (pin "8") (pinfunction "DB1_8") (pintype "bidirectional+no_connect"))
    )
    (net (code "51") (name "unconnected-(LCD1-DB2-Pad9)") (class "Default")
      (node (ref "LCD1") (pin "9") (pinfunction "DB2_9") (pintype "bidirectional+no_connect"))
    )
    (net (code "52") (name "unconnected-(LCD1-DB3-Pad10)") (class "Default")
      (node (ref "LCD1") (pin "10") (pinfunction "DB3_10") (pintype "bidirectional+no_connect"))
    )
    (net (code "53") (name "unconnected-(U1-CDC-Pad3)") (class "Default")
      (node (ref "U1") (pin "3") (pinfunction "CDC_3") (pintype "output+no_connect"))
    )
    (net (code "54") (name "unconnected-(U1-PWRGD-Pad15)") (class "Default")
      (node (ref "U1") (pin "15") (pinfunction "PWRGD_15") (pintype "output+no_connect"))
    )
    (net (code "55") (name "unconnected-(U1-RPWRGD-Pad4)") (class "Default")
      (node (ref "U1") (pin "4") (pinfunction "RPWRGD_4") (pintype "input+no_connect"))
    )
    (net (code "56") (name "unconnected-(U1-TEMP-Pad13)") (class "Default")
      (node (ref "U1") (pin "13") (pinfunction "TEMP_13") (pintype "output+no_connect"))
    )
    (net (code "57") (name "unconnected-(U1-TRACK-Pad14)") (class "Default")
      (node (ref "U1") (pin "14") (pinfunction "TRACK_14") (pintype "input+no_connect"))
    )
    (net (code "58") (name "unconnected-(U6-RA3{slash}AN3{slash}VREF+-Pad5)") (class "Default")
      (node (ref "U6") (pin "5") (pinfunction "RA3/AN3/VREF+_5") (pintype "bidirectional+no_connect"))
    )
    (net (code "59") (name "unconnected-(U6-RA4{slash}T0CKI{slash}C1OUT-Pad6)") (class "Default")
      (node (ref "U6") (pin "6") (pinfunction "RA4/T0CKI/C1OUT_6") (pintype "bidirectional+no_connect"))
    )
    (net (code "60") (name "unconnected-(U6-RA5{slash}AN4{slash}~{SS}{slash}C2OUT-Pad7)") (class "Default")
      (node (ref "U6") (pin "7") (pinfunction "RA5/AN4/~{SS}/C2OUT_7") (pintype "bidirectional+no_connect"))
    )
    (net (code "61") (name "unconnected-(U6-RB0{slash}INT-Pad21)") (class "Default")
      (node (ref "U6") (pin "21") (pinfunction "RB0/INT_21") (pintype "bidirectional+no_connect"))
    )
    (net (code "62") (name "unconnected-(U6-RB1-Pad22)") (class "Default")
      (node (ref "U6") (pin "22") (pinfunction "RB1_22") (pintype "bidirectional+no_connect"))
    )
    (net (code "63") (name "unconnected-(U6-RB2-Pad23)") (class "Default")
      (node (ref "U6") (pin "23") (pinfunction "RB2_23") (pintype "bidirectional+no_connect"))
    )
    (net (code "64") (name "unconnected-(U6-RB4-Pad25)") (class "Default")
      (node (ref "U6") (pin "25") (pinfunction "RB4_25") (pintype "bidirectional+no_connect"))
    )
    (net (code "65") (name "unconnected-(U6-RB5-Pad26)") (class "Default")
      (node (ref "U6") (pin "26") (pinfunction "RB5_26") (pintype "bidirectional+no_connect"))
    )
    (net (code "66") (name "unconnected-(U6-RC2{slash}CCP1-Pad13)") (class "Default")
      (node (ref "U6") (pin "13") (pinfunction "RC2/CCP1_13") (pintype "bidirectional"))
    )
    (net (code "67") (name "unconnected-(U6-RC3{slash}SCK{slash}SCL-Pad14)") (class "Default")
      (node (ref "U6") (pin "14") (pinfunction "RC3/SCK/SCL_14") (pintype "bidirectional"))
    )
  )
)
